# fulladder.net
KiCad netlist of a schematic drawn in EAGLE
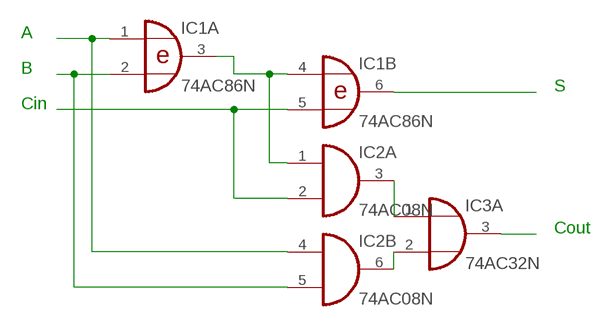
[diagram p0: schematic, sheet 1]

(export (version "E")
  (design (tool "Eeschema 10.0.6"))
  (components
    (comp (ref "IC1")
      (value "74AC86N")
      (footprint "eagle-import:DIL14")
      (libsource (lib "eagle-import") (part "7486NAC"))
    )
    (comp (ref "IC2")
      (value "74AC08N")
      (footprint "eagle-import:DIL14")
      (libsource (lib "eagle-import") (part "7408NAC"))
    )
    (comp (ref "IC3")
      (value "74AC32N")
      (footprint "eagle-import:DIL14")
      (libsource (lib "eagle-import") (part "7432NAC"))
    )
  )
  (nets
    (net (code "1") (name "Net-(IC1A-I0)") (class "Default")
      (node (ref "IC1") (pin "1") (pinfunction "I0_1") (pintype "input"))
      (node (ref "IC2") (pin "4") (pinfunction "I0_4") (pintype "input"))
    )
    (net (code "2") (name "Net-(IC1A-I1)") (class "Default")
      (node (ref "IC1") (pin "2") (pinfunction "I1_2") (pintype "input"))
      (node (ref "IC2") (pin "5") (pinfunction "I1_5") (pintype "input"))
    )
    (net (code "3") (name "Net-(IC1A-O)") (class "Default")
      (node (ref "IC1") (pin "3") (pinfunction "O_3") (pintype "output"))
      (node (ref "IC1") (pin "4") (pinfunction "I0_4") (pintype "input"))
      (node (ref "IC2") (pin "1") (pinfunction "I0_1") (pintype "input"))
    )
    (net (code "4") (name "Net-(IC1B-I1)") (class "Default")
      (node (ref "IC1") (pin "5") (pinfunction "I1_5") (pintype "input"))
      (node (ref "IC2") (pin "2") (pinfunction "I1_2") (pintype "input"))
    )
    (net (code "5") (name "Net-(IC2A-O)") (class "Default")
      (node (ref "IC2") (pin "3") (pinfunction "O_3") (pintype "output"))
      (node (ref "IC3") (pin "1") (pinfunction "I0_1") (pintype "input"))
    )
    (net (code "6") (name "Net-(IC2B-O)") (class "Default")
      (node (ref "IC2") (pin "6") (pinfunction "O_6") (pintype "output"))
      (node (ref "IC3") (pin "2") (pinfunction "I1_2") (pintype "input"))
    )
    (net (code "7") (name "unconnected-(IC1B-O-Pad6)") (class "Default")
      (node (ref "IC1") (pin "6") (pinfunction "O_6") (pintype "output"))
    )
    (net (code "8") (name "unconnected-(IC3A-O-Pad3)") (class "Default")
      (node (ref "IC3") (pin "3") (pinfunction "O_3") (pintype "output"))
    )
  )
)
